# Sheet1.net
KiCad netlist of a schematic drawn in Altium Designer
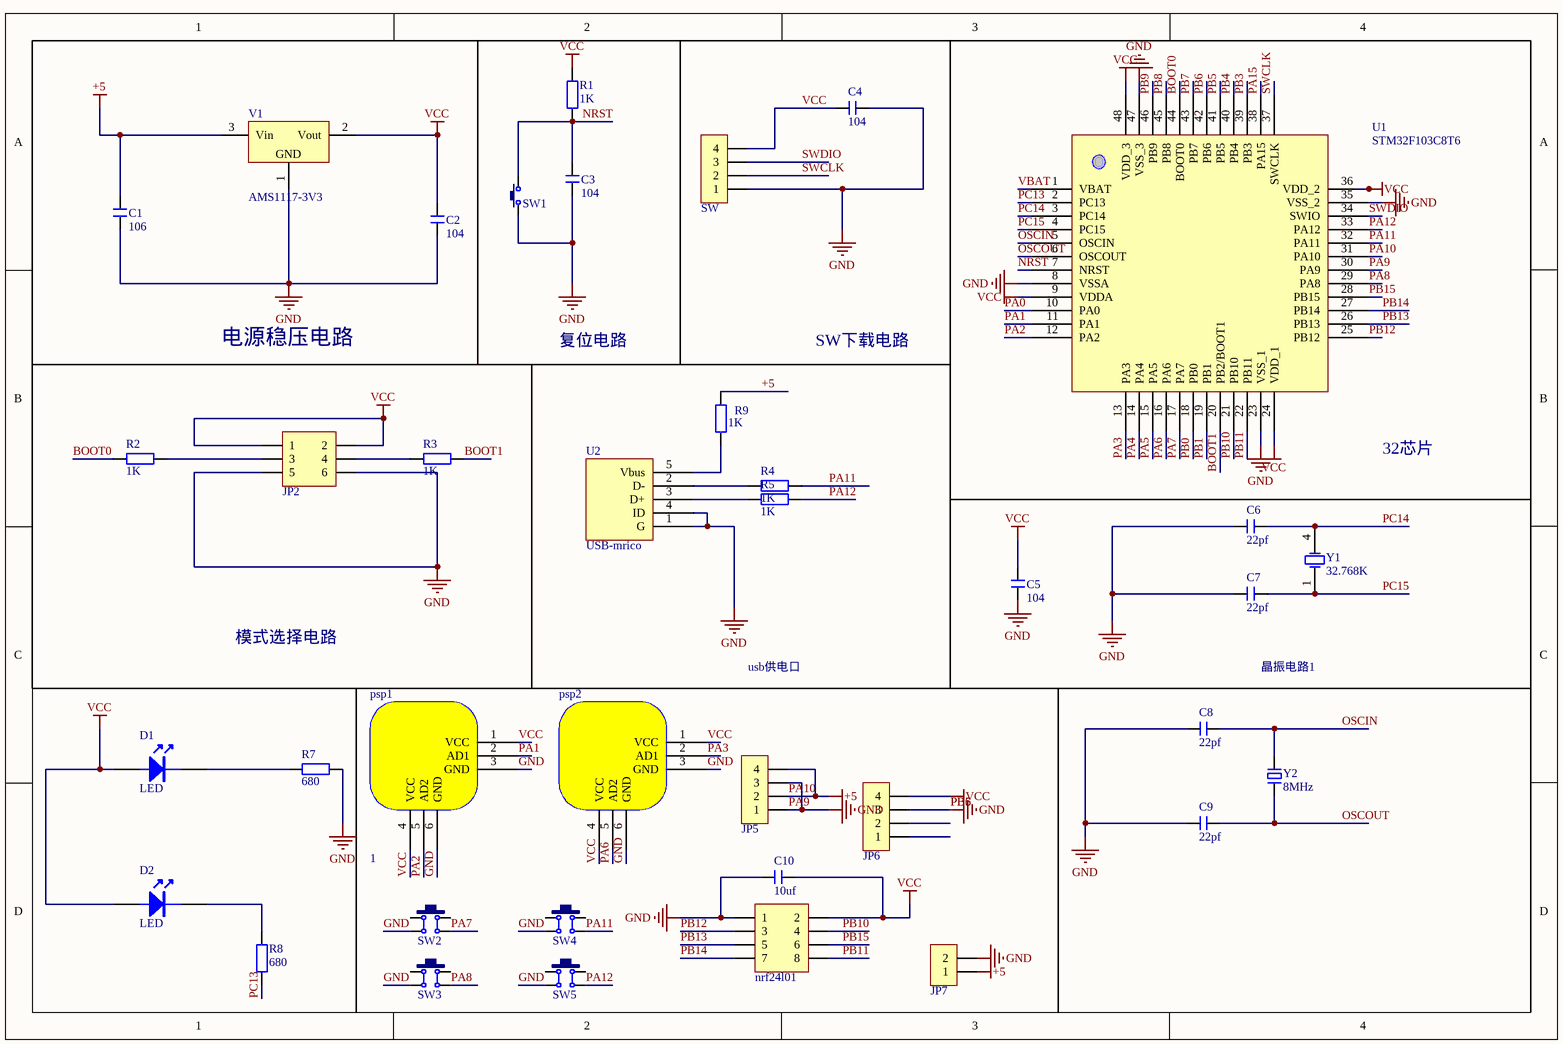
[diagram p0: Sheet1.SchDoc]

(export (version "E")
  (design (tool "Eeschema 10.0.6"))
  (components
    (comp (ref "C1")
      (value "106")
      (footprint "C 0805_L")
      (description "贴片电容")
      (libsource (lib "0.1 - 电阻-电容-电感") (part "C"))
    )
    (comp (ref "C2")
      (value "104")
      (footprint "C 0805_L")
      (description "贴片电容")
      (libsource (lib "0.1 - 电阻-电容-电感") (part "C"))
    )
    (comp (ref "C3")
      (value "104")
      (footprint "C 0805_L")
      (description "贴片电容")
      (libsource (lib "0.1 - 电阻-电容-电感") (part "C"))
    )
    (comp (ref "C4")
      (value "104")
      (footprint "C 0805_L")
      (description "贴片电容")
      (libsource (lib "0.1 - 电阻-电容-电感") (part "C"))
    )
    (comp (ref "C5")
      (value "104")
      (footprint "C 0805_L")
      (description "贴片电容")
      (libsource (lib "0.1 - 电阻-电容-电感") (part "C"))
    )
    (comp (ref "C6")
      (value "22pf")
      (footprint "C 0805_L")
      (description "贴片电容")
      (libsource (lib "0.1 - 电阻-电容-电感") (part "C"))
    )
    (comp (ref "C7")
      (value "22pf")
      (footprint "C 0805_L")
      (description "贴片电容")
      (libsource (lib "0.1 - 电阻-电容-电感") (part "C"))
    )
    (comp (ref "C8")
      (value "22pf")
      (footprint "C 0805_L")
      (description "贴片电容")
      (libsource (lib "0.1 - 电阻-电容-电感") (part "C"))
    )
    (comp (ref "C9")
      (value "22pf")
      (footprint "C 0805_L")
      (description "贴片电容")
      (libsource (lib "0.1 - 电阻-电容-电感") (part "C"))
    )
    (comp (ref "C10")
      (value "10uf")
      (footprint "C 0805_L")
      (description "贴片电容")
      (libsource (lib "0.1 - 电阻-电容-电感") (part "C"))
    )
    (comp (ref "D1") (value "LED") (footprint "LED 0805G") (libsource (lib "stm32原理图库") (part "LED")))
    (comp (ref "D2") (value "LED") (footprint "LED 0805G") (libsource (lib "stm32原理图库") (part "LED")))
    (comp (ref "JP2")
      (value "Header3X2")
      (footprint "HDR2.54-LI-2x3P")
      (description "3*2P接插件")
      (fields (field (name "版权归属") "封装库来自淘宝 ID：黄晶宝石"))
      (libsource (lib "5.3 - 接插件-脚距2.54 (100mil) ") (part "Header 3X2"))
    )
    (comp (ref "JP5")
      (value "HDR-1X4")
      (footprint "HDR2.54-M-LI-4P")
      (description "4P接插件")
      (fields (field (name "版权归属") "封装库来自淘宝 ID：黄晶宝石"))
      (libsource (lib "5.3 - 接插件-脚距2.54 (100mil) ") (part "Header 4"))
    )
    (comp (ref "JP6")
      (value "HDR-1X4")
      (footprint "HDR2.54-M-LI-4P")
      (description "4P接插件")
      (fields (field (name "版权归属") "封装库来自淘宝 ID：黄晶宝石"))
      (libsource (lib "5.3 - 接插件-脚距2.54 (100mil) ") (part "Header 4"))
    )
    (comp (ref "JP7")
      (value "HDR-1X2")
      (footprint "HDR2.54-WI-2P")
      (description "2P接插件")
      (fields (field (name "版权归属") "封装库来自淘宝 ID：黄晶宝石"))
      (libsource (lib "5.3 - 接插件-脚距2.54 (100mil) ") (part "Header 2"))
    )
    (comp (ref "nrf24l01")
      (value "Header 4X2")
      (footprint "HDR2.54-LI-2x4P")
      (description "4*2P接插件")
      (fields (field (name "版权归属") "封装库来自淘宝 ID：黄晶宝石"))
      (libsource (lib "5.3 - 接插件-脚距2.54 (100mil) ") (part "Header 4X2"))
    )
    (comp (ref "psp1") (value "1") (footprint "PSP摇杆") (libsource (lib "PSP摇杆") (part "PSP摇杆")))
    (comp (ref "psp2") (value "~") (footprint "PSP摇杆") (libsource (lib "PSP摇杆") (part "PSP摇杆")))
    (comp (ref "R1")
      (value "1K")
      (footprint "R 0805_L")
      (description "贴片电阻")
      (fields (field (name "版权归属") "来自淘宝 ID：黄晶宝石"))
      (libsource (lib "0.1 - 电阻-电容-电感") (part "R"))
    )
    (comp (ref "R2")
      (value "1K")
      (footprint "R 0805_L")
      (description "贴片电阻")
      (fields (field (name "版权归属") "来自淘宝 ID：黄晶宝石"))
      (libsource (lib "0.1 - 电阻-电容-电感") (part "R"))
    )
    (comp (ref "R3")
      (value "1K")
      (footprint "R 0805_L")
      (description "贴片电阻")
      (fields (field (name "版权归属") "来自淘宝 ID：黄晶宝石"))
      (libsource (lib "0.1 - 电阻-电容-电感") (part "R"))
    )
    (comp (ref "R4")
      (value "1K")
      (footprint "R 0805_L")
      (description "贴片电阻")
      (fields (field (name "版权归属") "来自淘宝 ID：黄晶宝石"))
      (libsource (lib "0.1 - 电阻-电容-电感") (part "R"))
    )
    (comp (ref "R5")
      (value "1K")
      (footprint "R 0805_L")
      (description "贴片电阻")
      (fields (field (name "版权归属") "来自淘宝 ID：黄晶宝石"))
      (libsource (lib "0.1 - 电阻-电容-电感") (part "R"))
    )
    (comp (ref "R7")
      (value "680")
      (footprint "R 0805_L")
      (description "贴片电阻")
      (fields (field (name "版权归属") "来自淘宝 ID：黄晶宝石"))
      (libsource (lib "0.1 - 电阻-电容-电感") (part "R"))
    )
    (comp (ref "R8")
      (value "680")
      (footprint "R 0805_L")
      (description "贴片电阻")
      (fields (field (name "版权归属") "来自淘宝 ID：黄晶宝石"))
      (libsource (lib "0.1 - 电阻-电容-电感") (part "R"))
    )
    (comp (ref "R9")
      (value "1K")
      (footprint "R 0805_L")
      (description "贴片电阻")
      (fields (field (name "版权归属") "来自淘宝 ID：黄晶宝石"))
      (libsource (lib "0.1 - 电阻-电容-电感") (part "R"))
    )
    (comp (ref "SW")
      (value "HDR-1X4")
      (footprint "HDR2.54-WI-4P")
      (description "4P接插件")
      (fields (field (name "版权归属") "封装库来自淘宝 ID：黄晶宝石"))
      (libsource (lib "5.3 - 接插件-脚距2.54 (100mil) ") (part "Header 4"))
    )
    (comp (ref "SW1")
      (value "3x6x5")
      (footprint "TSW SMD-3*6*2.5")
      (description "3x6轻触开关")
      (fields (field (name "版权归属") "封装库来自淘宝 ID：黄晶宝石"))
      (libsource (lib "0.7 - 常用按键-开关") (part "TSW 3x6"))
    )
    (comp (ref "SW2")
      (value "6x6x5")
      (footprint "TSW DIP-6*6*6")
      (description "直插6x6轻触开关")
      (fields (field (name "版权归属") "封装库来自淘宝 ID：黄晶宝石"))
      (libsource (lib "0.7 - 常用按键-开关") (part "TSW DIP-6x6"))
    )
    (comp (ref "SW3")
      (value "6x6x5")
      (footprint "TSW DIP-6*6*6")
      (description "直插6x6轻触开关")
      (fields (field (name "版权归属") "封装库来自淘宝 ID：黄晶宝石"))
      (libsource (lib "0.7 - 常用按键-开关") (part "TSW DIP-6x6"))
    )
    (comp (ref "SW4")
      (value "6x6x5")
      (footprint "TSW DIP-6*6*6")
      (description "直插6x6轻触开关")
      (fields (field (name "版权归属") "封装库来自淘宝 ID：黄晶宝石"))
      (libsource (lib "0.7 - 常用按键-开关") (part "TSW DIP-6x6"))
    )
    (comp (ref "SW5")
      (value "6x6x5")
      (footprint "TSW DIP-6*6*6")
      (description "直插6x6轻触开关")
      (fields (field (name "版权归属") "封装库来自淘宝 ID：黄晶宝石"))
      (libsource (lib "0.7 - 常用按键-开关") (part "TSW DIP-6x6"))
    )
    (comp (ref "U1")
      (value "STM32F103C8T6")
      (footprint "TQFP48 7x7_L")
      (libsource (lib "stm32原理图库") (part "STM32F103C8T6"))
    )
    (comp (ref "U2")
      (value "USB-mrico")
      (footprint "USB-micro_B")
      (libsource (lib "stm32原理图库") (part "usb-STM"))
    )
    (comp (ref "V1")
      (value "AMS1117-3V3")
      (footprint "SOT223_L")
      (description "三端稳压芯片")
      (libsource (lib "1.1 - 电源类芯片") (part "AMS1117"))
    )
    (comp (ref "Y1")
      (value "32.768K")
      (footprint "MC-306")
      (fields (field (name "PUBLISHER") "Altium Limited"))
      (libsource (lib "stm32原理图库") (part "XTAL"))
    )
    (comp (ref "Y2")
      (value "8MHz")
      (footprint "OSC HC-49S")
      (description "2脚无源脚晶振")
      (fields (field (name "版权归属") "封装库来自淘宝卖家 ID：黄晶宝石"))
      (libsource (lib "2.0 - 保险丝-晶振-光耦") (part "XTAL-2P"))
    )
  )
  (nets
    (net (code "1") (name "+5") (class "Default")
      (node (ref "C1") (pin "2") (pinfunction "2_2") (pintype "passive"))
      (node (ref "JP5") (pin "2") (pinfunction "2_2") (pintype "passive"))
      (node (ref "JP5") (pin "4") (pinfunction "4_4") (pintype "passive"))
      (node (ref "JP7") (pin "1") (pinfunction "1_1") (pintype "passive"))
      (node (ref "R9") (pin "2") (pinfunction "2_2") (pintype "passive"))
      (node (ref "U1") (pin "31") (pinfunction "PA10_31") (pintype "passive"))
      (node (ref "V1") (pin "3") (pinfunction "Vin_3") (pintype "passive"))
    )
    (net (code "3") (name "/BOOT0") (class "Default")
      (node (ref "R2") (pin "1") (pinfunction "1_1") (pintype "passive"))
      (node (ref "U1") (pin "44") (pinfunction "BOOT0_44") (pintype "passive"))
    )
    (net (code "4") (name "/BOOT1") (class "Default")
      (node (ref "R3") (pin "2") (pinfunction "2_2") (pintype "passive"))
      (node (ref "U1") (pin "20") (pinfunction "PB2/BOOT1_20") (pintype "passive"))
    )
    (net (code "5") (name "/NRST") (class "Default")
      (node (ref "C3") (pin "2") (pinfunction "2_2") (pintype "passive"))
      (node (ref "R1") (pin "1") (pinfunction "1_1") (pintype "passive"))
      (node (ref "SW1") (pin "2") (pinfunction "2_2") (pintype "passive"))
      (node (ref "U1") (pin "7") (pinfunction "NRST_7") (pintype "passive"))
    )
    (net (code "6") (name "/OSCIN") (class "Default")
      (node (ref "C8") (pin "2") (pinfunction "2_2") (pintype "passive"))
      (node (ref "U1") (pin "5") (pinfunction "OSCIN_5") (pintype "passive"))
      (node (ref "Y2") (pin "2") (pinfunction "2_2") (pintype "passive"))
    )
    (net (code "7") (name "/OSCOUT") (class "Default")
      (node (ref "C9") (pin "2") (pinfunction "2_2") (pintype "passive"))
      (node (ref "U1") (pin "6") (pinfunction "OSCOUT_6") (pintype "passive"))
      (node (ref "Y2") (pin "1") (pinfunction "1_1") (pintype "passive"))
    )
    (net (code "8") (name "/PA0") (class "Default")
      (node (ref "U1") (pin "10") (pinfunction "PA0_10") (pintype "passive"))
    )
    (net (code "9") (name "/PA1") (class "Default")
      (node (ref "U1") (pin "11") (pinfunction "PA1_11") (pintype "passive"))
      (node (ref "psp1") (pin "2") (pinfunction "AD1_2") (pintype "passive"))
    )
    (net (code "10") (name "/PA2") (class "Default")
      (node (ref "U1") (pin "12") (pinfunction "PA2_12") (pintype "passive"))
      (node (ref "psp1") (pin "5") (pinfunction "AD2_5") (pintype "passive"))
    )
    (net (code "11") (name "/PA3") (class "Default")
      (node (ref "U1") (pin "13") (pinfunction "PA3_13") (pintype "passive"))
      (node (ref "psp2") (pin "2") (pinfunction "AD1_2") (pintype "passive"))
    )
    (net (code "12") (name "/PA4") (class "Default")
      (node (ref "U1") (pin "14") (pinfunction "PA4_14") (pintype "passive"))
    )
    (net (code "13") (name "/PA5") (class "Default")
      (node (ref "U1") (pin "15") (pinfunction "PA5_15") (pintype "passive"))
    )
    (net (code "14") (name "/PA6") (class "Default")
      (node (ref "U1") (pin "16") (pinfunction "PA6_16") (pintype "passive"))
      (node (ref "psp2") (pin "5") (pinfunction "AD2_5") (pintype "passive"))
    )
    (net (code "15") (name "/PA7") (class "Default")
      (node (ref "SW2") (pin "3") (pinfunction "3_3") (pintype "passive"))
      (node (ref "U1") (pin "17") (pinfunction "PA7_17") (pintype "passive"))
    )
    (net (code "16") (name "/PA8") (class "Default")
      (node (ref "SW3") (pin "3") (pinfunction "3_3") (pintype "passive"))
      (node (ref "U1") (pin "29") (pinfunction "PA8_29") (pintype "passive"))
    )
    (net (code "17") (name "/PA11") (class "Default")
      (node (ref "R4") (pin "2") (pinfunction "2_2") (pintype "passive"))
      (node (ref "SW4") (pin "3") (pinfunction "3_3") (pintype "passive"))
      (node (ref "U1") (pin "32") (pinfunction "PA11_32") (pintype "passive"))
    )
    (net (code "18") (name "/PA12") (class "Default")
      (node (ref "R5") (pin "2") (pinfunction "2_2") (pintype "passive"))
      (node (ref "SW5") (pin "3") (pinfunction "3_3") (pintype "passive"))
      (node (ref "U1") (pin "33") (pinfunction "PA12_33") (pintype "passive"))
    )
    (net (code "19") (name "/PA15") (class "Default")
      (node (ref "U1") (pin "38") (pinfunction "PA15_38") (pintype "passive"))
    )
    (net (code "20") (name "/PB0") (class "Default")
      (node (ref "U1") (pin "18") (pinfunction "PB0_18") (pintype "passive"))
    )
    (net (code "21") (name "/PB1") (class "Default")
      (node (ref "U1") (pin "19") (pinfunction "PB1_19") (pintype "passive"))
    )
    (net (code "22") (name "/PB3") (class "Default")
      (node (ref "U1") (pin "39") (pinfunction "PB3_39") (pintype "passive"))
    )
    (net (code "23") (name "/PB4") (class "Default")
      (node (ref "U1") (pin "40") (pinfunction "PB4_40") (pintype "passive"))
    )
    (net (code "24") (name "/PB7") (class "Default")
      (node (ref "U1") (pin "43") (pinfunction "PB7_43") (pintype "passive"))
    )
    (net (code "25") (name "/PB8") (class "Default")
      (node (ref "U1") (pin "45") (pinfunction "PB8_45") (pintype "passive"))
    )
    (net (code "26") (name "/PB9") (class "Default")
      (node (ref "U1") (pin "46") (pinfunction "PB9_46") (pintype "passive"))
    )
    (net (code "27") (name "/PB10") (class "Default")
      (node (ref "U1") (pin "21") (pinfunction "PB10_21") (pintype "passive"))
      (node (ref "nrf24l01") (pin "4") (pinfunction "4_4") (pintype "passive"))
    )
    (net (code "28") (name "/PB11") (class "Default")
      (node (ref "U1") (pin "22") (pinfunction "PB11_22") (pintype "passive"))
      (node (ref "nrf24l01") (pin "8") (pinfunction "8_8") (pintype "passive"))
    )
    (net (code "29") (name "/PB12") (class "Default")
      (node (ref "U1") (pin "25") (pinfunction "PB12_25") (pintype "passive"))
      (node (ref "nrf24l01") (pin "3") (pinfunction "3_3") (pintype "passive"))
    )
    (net (code "30") (name "/PB13") (class "Default")
      (node (ref "U1") (pin "26") (pinfunction "PB13_26") (pintype "passive"))
      (node (ref "nrf24l01") (pin "5") (pinfunction "5_5") (pintype "passive"))
    )
    (net (code "31") (name "/PB14") (class "Default")
      (node (ref "U1") (pin "27") (pinfunction "PB14_27") (pintype "passive"))
      (node (ref "nrf24l01") (pin "7") (pinfunction "7_7") (pintype "passive"))
    )
    (net (code "32") (name "/PB15") (class "Default")
      (node (ref "U1") (pin "28") (pinfunction "PB15_28") (pintype "passive"))
      (node (ref "nrf24l01") (pin "6") (pinfunction "6_6") (pintype "passive"))
    )
    (net (code "33") (name "/PC13") (class "Default")
      (node (ref "R8") (pin "2") (pinfunction "2_2") (pintype "passive"))
      (node (ref "U1") (pin "2") (pinfunction "PC13_2") (pintype "passive"))
    )
    (net (code "34") (name "/PC14") (class "Default")
      (node (ref "C6") (pin "1") (pinfunction "1_1") (pintype "passive"))
      (node (ref "U1") (pin "3") (pinfunction "PC14_3") (pintype "passive"))
      (node (ref "Y1") (pin "4") (pinfunction "OSC2_4") (pintype "passive"))
    )
    (net (code "35") (name "/PC15") (class "Default")
      (node (ref "C7") (pin "1") (pinfunction "1_1") (pintype "passive"))
      (node (ref "U1") (pin "4") (pinfunction "PC15_4") (pintype "passive"))
      (node (ref "Y1") (pin "1") (pinfunction "OSC1_1") (pintype "passive"))
    )
    (net (code "36") (name "/SWCLK") (class "Default")
      (node (ref "SW") (pin "2") (pinfunction "2_2") (pintype "passive"))
      (node (ref "U1") (pin "37") (pinfunction "SWCLK_37") (pintype "passive"))
    )
    (net (code "37") (name "/SWDIO") (class "Default")
      (node (ref "SW") (pin "3") (pinfunction "3_3") (pintype "passive"))
      (node (ref "U1") (pin "34") (pinfunction "SWIO_34") (pintype "passive"))
    )
    (net (code "38") (name "/VBAT") (class "Default")
      (node (ref "U1") (pin "1") (pinfunction "VBAT_1") (pintype "passive"))
    )
    (net (code "39") (name "GND") (class "Default")
      (node (ref "C1") (pin "1") (pinfunction "1_1") (pintype "passive"))
      (node (ref "C10") (pin "1") (pinfunction "1_1") (pintype "passive"))
      (node (ref "C2") (pin "1") (pinfunction "1_1") (pintype "passive"))
      (node (ref "C3") (pin "1") (pinfunction "1_1") (pintype "passive"))
      (node (ref "C4") (pin "1") (pinfunction "1_1") (pintype "passive"))
      (node (ref "C5") (pin "1") (pinfunction "1_1") (pintype "passive"))
      (node (ref "C6") (pin "2") (pinfunction "2_2") (pintype "passive"))
      (node (ref "C7") (pin "2") (pinfunction "2_2") (pintype "passive"))
      (node (ref "C8") (pin "1") (pinfunction "1_1") (pintype "passive"))
      (node (ref "C9") (pin "1") (pinfunction "1_1") (pintype "passive"))
      (node (ref "JP2") (pin "5") (pinfunction "5_5") (pintype "passive"))
      (node (ref "JP2") (pin "6") (pinfunction "6_6") (pintype "passive"))
      (node (ref "JP5") (pin "1") (pinfunction "1_1") (pintype "passive"))
      (node (ref "JP5") (pin "3") (pinfunction "3_3") (pintype "passive"))
      (node (ref "JP6") (pin "3") (pinfunction "3_3") (pintype "passive"))
      (node (ref "JP7") (pin "2") (pinfunction "2_2") (pintype "passive"))
      (node (ref "R7") (pin "1") (pinfunction "1_1") (pintype "passive"))
      (node (ref "SW") (pin "1") (pinfunction "1_1") (pintype "passive"))
      (node (ref "SW1") (pin "1") (pinfunction "1_1") (pintype "passive"))
      (node (ref "SW2") (pin "4") (pinfunction "4_4") (pintype "passive"))
      (node (ref "SW3") (pin "4") (pinfunction "4_4") (pintype "passive"))
      (node (ref "SW4") (pin "4") (pinfunction "4_4") (pintype "passive"))
      (node (ref "SW5") (pin "4") (pinfunction "4_4") (pintype "passive"))
      (node (ref "U1") (pin "23") (pinfunction "VSS_1_23") (pintype "passive"))
      (node (ref "U1") (pin "30") (pinfunction "PA9_30") (pintype "passive"))
      (node (ref "U1") (pin "35") (pinfunction "VSS_2_35") (pintype "passive"))
      (node (ref "U1") (pin "41") (pinfunction "PB5_41") (pintype "passive"))
      (node (ref "U1") (pin "42") (pinfunction "PB6_42") (pintype "passive"))
      (node (ref "U1") (pin "47") (pinfunction "VSS_3_47") (pintype "passive"))
      (node (ref "U1") (pin "8") (pinfunction "VSSA_8") (pintype "passive"))
      (node (ref "U2") (pin "1") (pinfunction "G_1") (pintype "passive"))
      (node (ref "U2") (pin "4") (pinfunction "ID_4") (pintype "passive"))
      (node (ref "V1") (pin "1") (pinfunction "GND_1") (pintype "passive"))
      (node (ref "nrf24l01") (pin "1") (pinfunction "1_1") (pintype "passive"))
      (node (ref "psp1") (pin "3") (pinfunction "GND_3") (pintype "passive"))
      (node (ref "psp1") (pin "6") (pinfunction "GND_6") (pintype "passive"))
      (node (ref "psp2") (pin "3") (pinfunction "GND_3") (pintype "passive"))
      (node (ref "psp2") (pin "6") (pinfunction "GND_6") (pintype "passive"))
    )
    (net (code "40") (name "Net-(D1-Pad2)") (class "Default")
      (node (ref "D1") (pin "2") (pinfunction "2_2") (pintype "passive"))
      (node (ref "R7") (pin "2") (pinfunction "2_2") (pintype "passive"))
    )
    (net (code "41") (name "Net-(D2-Pad2)") (class "Default")
      (node (ref "D2") (pin "2") (pinfunction "2_2") (pintype "passive"))
      (node (ref "R8") (pin "1") (pinfunction "1_1") (pintype "passive"))
    )
    (net (code "42") (name "Net-(JP2-Pad3)") (class "Default")
      (node (ref "JP2") (pin "3") (pinfunction "3_3") (pintype "passive"))
      (node (ref "R2") (pin "2") (pinfunction "2_2") (pintype "passive"))
    )
    (net (code "43") (name "Net-(JP2-Pad4)") (class "Default")
      (node (ref "JP2") (pin "4") (pinfunction "4_4") (pintype "passive"))
      (node (ref "R3") (pin "1") (pinfunction "1_1") (pintype "passive"))
    )
    (net (code "44") (name "Net-(U2-D+)") (class "Default")
      (node (ref "R5") (pin "1") (pinfunction "1_1") (pintype "passive"))
      (node (ref "U2") (pin "3") (pinfunction "D+_3") (pintype "passive"))
    )
    (net (code "45") (name "Net-(U2-D-)") (class "Default")
      (node (ref "R4") (pin "1") (pinfunction "1_1") (pintype "passive"))
      (node (ref "U2") (pin "2") (pinfunction "D-_2") (pintype "passive"))
    )
    (net (code "46") (name "Net-(U2-Vbus)") (class "Default")
      (node (ref "R9") (pin "1") (pinfunction "1_1") (pintype "passive"))
      (node (ref "U2") (pin "5") (pinfunction "Vbus_5") (pintype "passive"))
    )
    (net (code "47") (name "VCC") (class "Default")
      (node (ref "C10") (pin "2") (pinfunction "2_2") (pintype "passive"))
      (node (ref "C2") (pin "2") (pinfunction "2_2") (pintype "passive"))
      (node (ref "C4") (pin "2") (pinfunction "2_2") (pintype "passive"))
      (node (ref "C5") (pin "2") (pinfunction "2_2") (pintype "passive"))
      (node (ref "D1") (pin "1") (pinfunction "1_1") (pintype "passive"))
      (node (ref "D2") (pin "1") (pinfunction "1_1") (pintype "passive"))
      (node (ref "JP2") (pin "1") (pinfunction "1_1") (pintype "passive"))
      (node (ref "JP2") (pin "2") (pinfunction "2_2") (pintype "passive"))
      (node (ref "JP6") (pin "4") (pinfunction "4_4") (pintype "passive"))
      (node (ref "R1") (pin "2") (pinfunction "2_2") (pintype "passive"))
      (node (ref "SW") (pin "4") (pinfunction "4_4") (pintype "passive"))
      (node (ref "U1") (pin "24") (pinfunction "VDD_1_24") (pintype "passive"))
      (node (ref "U1") (pin "36") (pinfunction "VDD_2_36") (pintype "passive"))
      (node (ref "U1") (pin "48") (pinfunction "VDD_3_48") (pintype "passive"))
      (node (ref "U1") (pin "9") (pinfunction "VDDA_9") (pintype "passive"))
      (node (ref "V1") (pin "2") (pinfunction "Vout_2") (pintype "passive"))
      (node (ref "nrf24l01") (pin "2") (pinfunction "2_2") (pintype "passive"))
      (node (ref "psp1") (pin "1") (pinfunction "VCC_1") (pintype "passive"))
      (node (ref "psp1") (pin "4") (pinfunction "VCC_4") (pintype "passive"))
      (node (ref "psp2") (pin "1") (pinfunction "VCC_1") (pintype "passive"))
      (node (ref "psp2") (pin "4") (pinfunction "VCC_4") (pintype "passive"))
    )
    (net (code "48") (name "unconnected-(JP6-Pad1)") (class "Default")
      (node (ref "JP6") (pin "1") (pinfunction "1_1") (pintype "passive"))
    )
    (net (code "49") (name "unconnected-(JP6-Pad2)") (class "Default")
      (node (ref "JP6") (pin "2") (pinfunction "2_2") (pintype "passive"))
    )
    (net (code "50") (name "unconnected-(SW2-Pad1)") (class "Default")
      (node (ref "SW2") (pin "1") (pinfunction "1_1") (pintype "passive"))
    )
    (net (code "51") (name "unconnected-(SW2-Pad2)") (class "Default")
      (node (ref "SW2") (pin "2") (pinfunction "2_2") (pintype "passive"))
    )
    (net (code "52") (name "unconnected-(SW3-Pad1)") (class "Default")
      (node (ref "SW3") (pin "1") (pinfunction "1_1") (pintype "passive"))
    )
    (net (code "53") (name "unconnected-(SW3-Pad2)") (class "Default")
      (node (ref "SW3") (pin "2") (pinfunction "2_2") (pintype "passive"))
    )
    (net (code "54") (name "unconnected-(SW4-Pad1)") (class "Default")
      (node (ref "SW4") (pin "1") (pinfunction "1_1") (pintype "passive"))
    )
    (net (code "55") (name "unconnected-(SW4-Pad2)") (class "Default")
      (node (ref "SW4") (pin "2") (pinfunction "2_2") (pintype "passive"))
    )
    (net (code "56") (name "unconnected-(SW5-Pad1)") (class "Default")
      (node (ref "SW5") (pin "1") (pinfunction "1_1") (pintype "passive"))
    )
    (net (code "57") (name "unconnected-(SW5-Pad2)") (class "Default")
      (node (ref "SW5") (pin "2") (pinfunction "2_2") (pintype "passive"))
    )
  )
)
